# sd.net
KiCad netlist of a schematic drawn in Altium Designer
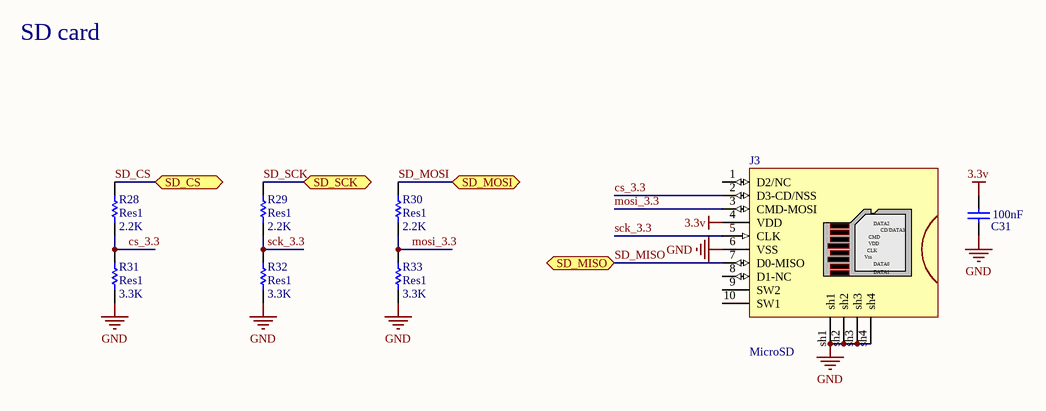
[diagram p0: sd.SchDoc]

(export (version "E")
  (design (tool "Eeschema 10.0.6"))
  (components
    (comp (ref "C31")
      (value "100nF")
      (footprint "CAP 1206 (3216X15L)")
      (description "CAP-100Nf")
      (fields (field (name "Comment") "Cap"))
      (libsource (lib "Altium library (www.AVRelec.com)") (part "Cap ceramic"))
    )
    (comp (ref "J3")
      (value "MicroSD")
      (footprint "SD_card")
      (description "MicroSD_altium designer (M.Hariri)")
      (fields (field (name "CREATED BY:") "altium designer (M.Hariri)"))
      (libsource (lib "MicroSD_altium designer") (part "MicroSD"))
    )
    (comp (ref "R28")
      (value "Res1")
      (footprint "RES 1206 (3216X08L)")
      (description "Resistor")
      (fields (field (name "ALTIUM_VALUE") "2.2K") (field (name "PUBLISHER") "Altium Limited"))
      (libsource (lib "Miscellaneous Devices") (part "Res1"))
    )
    (comp (ref "R29")
      (value "Res1")
      (footprint "RES 1206 (3216X08L)")
      (description "Resistor")
      (fields (field (name "ALTIUM_VALUE") "2.2K") (field (name "PUBLISHER") "Altium Limited"))
      (libsource (lib "Miscellaneous Devices") (part "Res1"))
    )
    (comp (ref "R30")
      (value "Res1")
      (footprint "RES 1206 (3216X08L)")
      (description "Resistor")
      (fields (field (name "ALTIUM_VALUE") "2.2K") (field (name "PUBLISHER") "Altium Limited"))
      (libsource (lib "Miscellaneous Devices") (part "Res1"))
    )
    (comp (ref "R31")
      (value "Res1")
      (footprint "RES 1206 (3216X08L)")
      (description "Resistor")
      (fields (field (name "ALTIUM_VALUE") "3.3K") (field (name "PUBLISHER") "Altium Limited"))
      (libsource (lib "Miscellaneous Devices") (part "Res1"))
    )
    (comp (ref "R32")
      (value "Res1")
      (footprint "RES 1206 (3216X08L)")
      (description "Resistor")
      (fields (field (name "ALTIUM_VALUE") "3.3K") (field (name "PUBLISHER") "Altium Limited"))
      (libsource (lib "Miscellaneous Devices") (part "Res1"))
    )
    (comp (ref "R33")
      (value "Res1")
      (footprint "RES 1206 (3216X08L)")
      (description "Resistor")
      (fields (field (name "ALTIUM_VALUE") "3.3K") (field (name "PUBLISHER") "Altium Limited"))
      (libsource (lib "Miscellaneous Devices") (part "Res1"))
    )
  )
  (nets
    (net (code "1") (name "/SD_CS") (class "Default")
      (node (ref "R28") (pin "2") (pinfunction "2_2") (pintype "passive"))
    )
    (net (code "2") (name "/SD_MISO") (class "Default")
      (node (ref "J3") (pin "7") (pinfunction "D0-MISO_7") (pintype "bidirectional"))
    )
    (net (code "3") (name "/SD_MOSI") (class "Default")
      (node (ref "R30") (pin "2") (pinfunction "2_2") (pintype "passive"))
    )
    (net (code "4") (name "/SD_SCK") (class "Default")
      (node (ref "R29") (pin "2") (pinfunction "2_2") (pintype "passive"))
    )
    (net (code "5") (name "/cs_3.3") (class "Default")
      (node (ref "J3") (pin "2") (pinfunction "D3-CD/NSS_2") (pintype "bidirectional"))
      (node (ref "R28") (pin "1") (pinfunction "1_1") (pintype "passive"))
      (node (ref "R31") (pin "2") (pinfunction "2_2") (pintype "passive"))
    )
    (net (code "6") (name "/mosi_3.3") (class "Default")
      (node (ref "J3") (pin "3") (pinfunction "CMD-MOSI_3") (pintype "bidirectional"))
      (node (ref "R30") (pin "1") (pinfunction "1_1") (pintype "passive"))
      (node (ref "R33") (pin "2") (pinfunction "2_2") (pintype "passive"))
    )
    (net (code "7") (name "/sck_3.3") (class "Default")
      (node (ref "J3") (pin "5") (pinfunction "CLK_5") (pintype "input"))
      (node (ref "R29") (pin "1") (pinfunction "1_1") (pintype "passive"))
      (node (ref "R32") (pin "2") (pinfunction "2_2") (pintype "passive"))
    )
    (net (code "8") (name "3.3v") (class "Default")
      (node (ref "C31") (pin "2") (pinfunction "2_2") (pintype "passive"))
      (node (ref "J3") (pin "4") (pinfunction "VDD_4") (pintype "power_in"))
    )
    (net (code "9") (name "GND") (class "Default")
      (node (ref "C31") (pin "1") (pinfunction "1_1") (pintype "passive"))
      (node (ref "J3") (pin "6") (pinfunction "VSS_6") (pintype "power_in"))
      (node (ref "J3") (pin "sh1") (pinfunction "sh1_sh1") (pintype "passive"))
      (node (ref "J3") (pin "sh2") (pinfunction "sh2_sh2") (pintype "passive"))
      (node (ref "J3") (pin "sh3") (pinfunction "sh3_sh3") (pintype "passive"))
      (node (ref "J3") (pin "sh4") (pinfunction "sh4_sh4") (pintype "passive"))
      (node (ref "R31") (pin "1") (pinfunction "1_1") (pintype "passive"))
      (node (ref "R32") (pin "1") (pinfunction "1_1") (pintype "passive"))
      (node (ref "R33") (pin "1") (pinfunction "1_1") (pintype "passive"))
    )
    (net (code "10") (name "unconnected-(J3-D1-NC-Pad8)") (class "Default")
      (node (ref "J3") (pin "8") (pinfunction "D1-NC_8") (pintype "bidirectional"))
    )
    (net (code "11") (name "unconnected-(J3-D2{slash}NC-Pad1)") (class "Default")
      (node (ref "J3") (pin "1") (pinfunction "D2/NC_1") (pintype "bidirectional"))
    )
    (net (code "12") (name "unconnected-(J3-SW1-Pad10)") (class "Default")
      (node (ref "J3") (pin "10") (pinfunction "SW1_10") (pintype "passive"))
    )
    (net (code "13") (name "unconnected-(J3-SW2-Pad9)") (class "Default")
      (node (ref "J3") (pin "9") (pinfunction "SW2_9") (pintype "passive"))
    )
  )
)
